# antduino.net
KiCad netlist of a schematic drawn in EAGLE
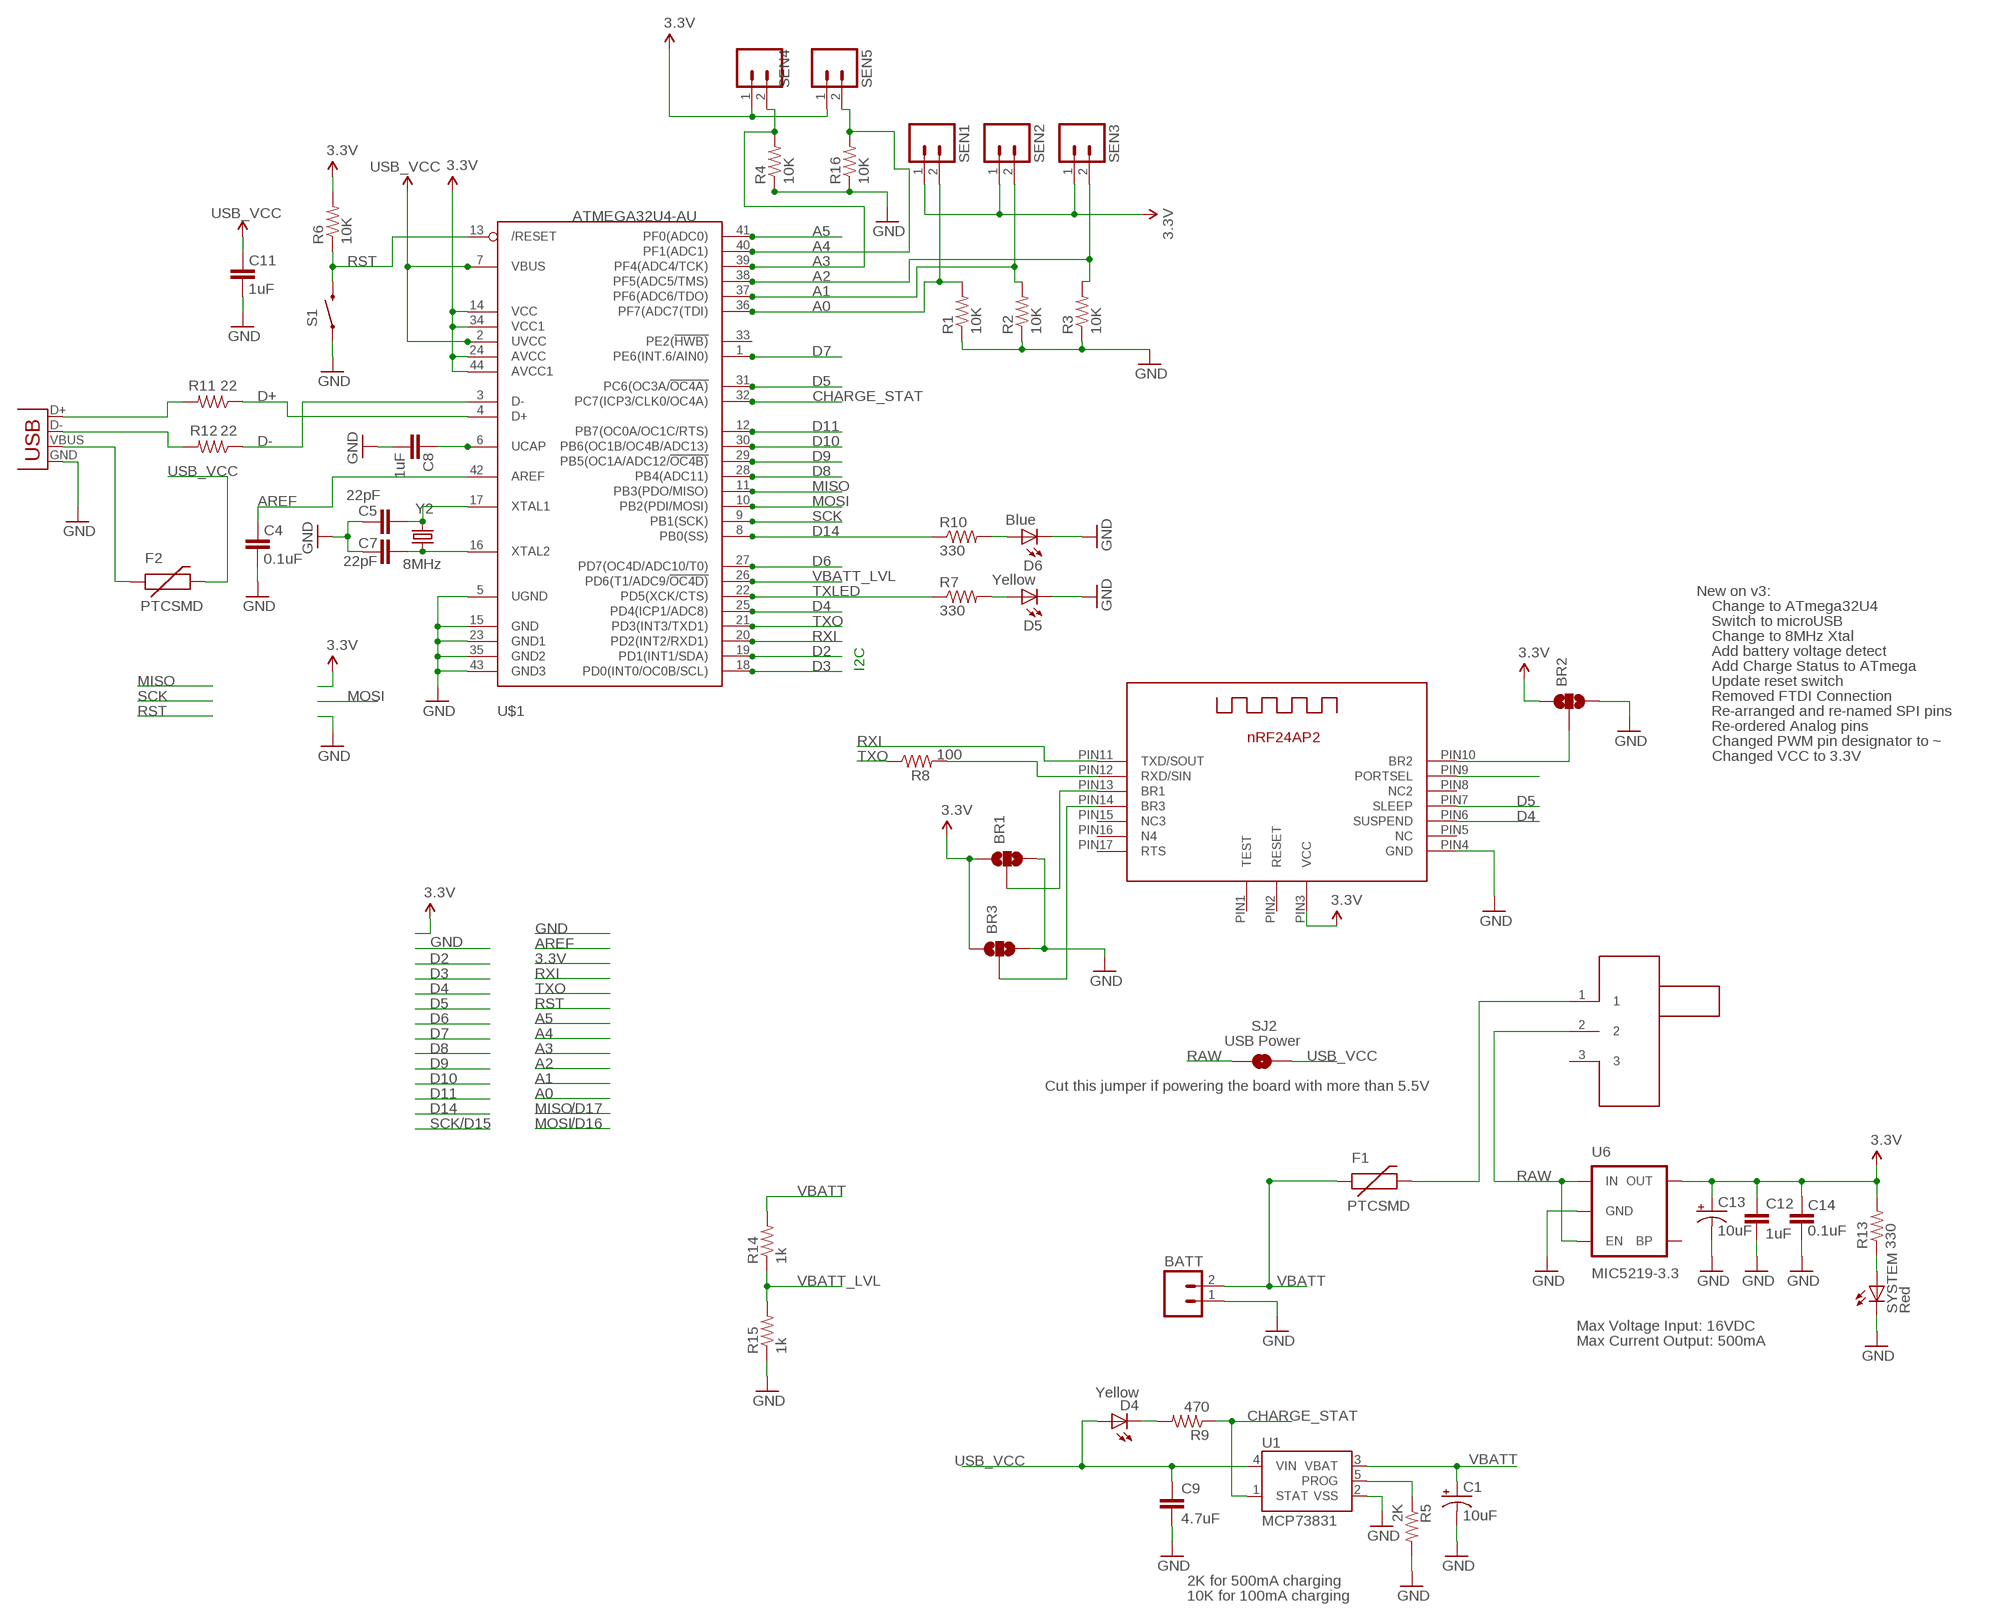
[diagram p0: schematic, sheet 1]

(export (version "E")
  (design (tool "Eeschema 10.0.6"))
  (components
    (comp (ref "BATT")
      (value "M02PTH")
      (footprint "eagle-import:1X02")
      (libsource (lib "eagle-import") (part "M02PTH"))
    )
    (comp (ref "BR1")
      (value "SOLDERJUMPER_2WAY-OLDS")
      (footprint "eagle-import:SJ_3")
      (libsource (lib "eagle-import") (part "SOLDERJUMPER_2WAY-OLDS"))
    )
    (comp (ref "BR2")
      (value "SOLDERJUMPER_2WAY-OLDS")
      (footprint "eagle-import:SJ_3")
      (libsource (lib "eagle-import") (part "SOLDERJUMPER_2WAY-OLDS"))
    )
    (comp (ref "BR3")
      (value "SOLDERJUMPER_2WAY-OLDS")
      (footprint "eagle-import:SJ_3")
      (libsource (lib "eagle-import") (part "SOLDERJUMPER_2WAY-OLDS"))
    )
    (comp (ref "C1")
      (value "10uF")
      (footprint "eagle-import:EIA3216")
      (libsource (lib "eagle-import") (part "CAP_POL1206"))
    )
    (comp (ref "C4")
      (value "0.1uF")
      (footprint "eagle-import:0402-CAP")
      (libsource (lib "eagle-import") (part "CAP0402-CAP"))
    )
    (comp (ref "C5")
      (value "22pF")
      (footprint "eagle-import:0402-CAP")
      (libsource (lib "eagle-import") (part "CAP0402-CAP"))
    )
    (comp (ref "C7")
      (value "22pF")
      (footprint "eagle-import:0402-CAP")
      (libsource (lib "eagle-import") (part "CAP0402-CAP"))
    )
    (comp (ref "C8")
      (value "1uF")
      (footprint "eagle-import:0402-CAP")
      (libsource (lib "eagle-import") (part "CAP0402-CAP"))
    )
    (comp (ref "C9")
      (value "4.7uF")
      (footprint "eagle-import:0402-CAP")
      (libsource (lib "eagle-import") (part "CAP0402-CAP"))
    )
    (comp (ref "C11")
      (value "1uF")
      (footprint "eagle-import:0402-CAP")
      (libsource (lib "eagle-import") (part "CAP0402-CAP"))
    )
    (comp (ref "C12")
      (value "1uF")
      (footprint "eagle-import:0402-CAP")
      (libsource (lib "eagle-import") (part "CAP0402-CAP"))
    )
    (comp (ref "C13")
      (value "10uF")
      (footprint "eagle-import:EIA3216")
      (libsource (lib "eagle-import") (part "CAP_POL1206"))
    )
    (comp (ref "C14")
      (value "0.1uF")
      (footprint "eagle-import:0402-CAP")
      (libsource (lib "eagle-import") (part "CAP0402-CAP"))
    )
    (comp (ref "D4")
      (value "Yellow")
      (footprint "eagle-import:LED-0603")
      (libsource (lib "eagle-import") (part "LED0603"))
    )
    (comp (ref "D5")
      (value "Yellow")
      (footprint "eagle-import:LED-0603")
      (libsource (lib "eagle-import") (part "LED0603"))
    )
    (comp (ref "D6")
      (value "Blue")
      (footprint "eagle-import:LED-0603")
      (libsource (lib "eagle-import") (part "LED0603"))
    )
    (comp (ref "F1")
      (value "PTCSMD")
      (footprint "eagle-import:PTC-1206")
      (libsource (lib "eagle-import") (part "PTCSMD"))
    )
    (comp (ref "F2")
      (value "PTCSMD")
      (footprint "eagle-import:PTC-1206")
      (libsource (lib "eagle-import") (part "PTCSMD"))
    )
    (comp (ref "R1")
      (value "10K")
      (footprint "eagle-import:0402-RES")
      (libsource (lib "eagle-import") (part "RESISTOR0402-RES"))
    )
    (comp (ref "R2")
      (value "10K")
      (footprint "eagle-import:0402-RES")
      (libsource (lib "eagle-import") (part "RESISTOR0402-RES"))
    )
    (comp (ref "R3")
      (value "10K")
      (footprint "eagle-import:0402-RES")
      (libsource (lib "eagle-import") (part "RESISTOR0402-RES"))
    )
    (comp (ref "R4")
      (value "10K")
      (footprint "eagle-import:0402-RES")
      (libsource (lib "eagle-import") (part "RESISTOR0402-RES"))
    )
    (comp (ref "R5")
      (value "2K")
      (footprint "eagle-import:0402-RES")
      (libsource (lib "eagle-import") (part "RESISTOR0402-RES"))
    )
    (comp (ref "R6")
      (value "10K")
      (footprint "eagle-import:0402-RES")
      (libsource (lib "eagle-import") (part "RESISTOR0402-RES"))
    )
    (comp (ref "R7")
      (value "330")
      (footprint "eagle-import:0402-RES")
      (libsource (lib "eagle-import") (part "RESISTOR0402-RES"))
    )
    (comp (ref "R8")
      (value "100")
      (footprint "eagle-import:0402-RES")
      (libsource (lib "eagle-import") (part "RESISTOR0402-RES"))
    )
    (comp (ref "R9")
      (value "470")
      (footprint "eagle-import:0402-RES")
      (libsource (lib "eagle-import") (part "RESISTOR0402-RES"))
    )
    (comp (ref "R10")
      (value "330")
      (footprint "eagle-import:0402-RES")
      (libsource (lib "eagle-import") (part "RESISTOR0402-RES"))
    )
    (comp (ref "R11")
      (value "22")
      (footprint "eagle-import:0402-RES")
      (libsource (lib "eagle-import") (part "RESISTOR0402-RES"))
    )
    (comp (ref "R12")
      (value "22")
      (footprint "eagle-import:0402-RES")
      (libsource (lib "eagle-import") (part "RESISTOR0402-RES"))
    )
    (comp (ref "R13")
      (value "330")
      (footprint "eagle-import:0402-RES")
      (libsource (lib "eagle-import") (part "RESISTOR0402-RES"))
    )
    (comp (ref "R14")
      (value "1k")
      (footprint "eagle-import:0402-RES")
      (libsource (lib "eagle-import") (part "RESISTOR0402-RES"))
    )
    (comp (ref "R15")
      (value "1k")
      (footprint "eagle-import:0402-RES")
      (libsource (lib "eagle-import") (part "RESISTOR0402-RES"))
    )
    (comp (ref "R16")
      (value "10K")
      (footprint "eagle-import:0402-RES")
      (libsource (lib "eagle-import") (part "RESISTOR0402-RES"))
    )
    (comp (ref "S1")
      (value "SWITCH-MOMENTARY-2-SMD-1101NE")
      (footprint "eagle-import:TACTILE-SWITCH-1101NE")
      (libsource (lib "eagle-import") (part "SWITCH-MOMENTARY-2-SMD-1101NE"))
    )
    (comp (ref "SEN1")
      (value "M02-JST-2MM-SMT")
      (footprint "eagle-import:JST-2-SMD")
      (libsource (lib "eagle-import") (part "M02-JST-2MM-SMT"))
    )
    (comp (ref "SEN2")
      (value "M02-JST-2MM-SMT")
      (footprint "eagle-import:JST-2-SMD")
      (libsource (lib "eagle-import") (part "M02-JST-2MM-SMT"))
    )
    (comp (ref "SEN3")
      (value "M02-JST-2MM-SMT")
      (footprint "eagle-import:JST-2-SMD")
      (libsource (lib "eagle-import") (part "M02-JST-2MM-SMT"))
    )
    (comp (ref "SEN4")
      (value "M02PTH")
      (footprint "eagle-import:1X02")
      (libsource (lib "eagle-import") (part "M02PTH"))
    )
    (comp (ref "SEN5")
      (value "M02PTH")
      (footprint "eagle-import:1X02")
      (libsource (lib "eagle-import") (part "M02PTH"))
    )
    (comp (ref "SJ2")
      (value "USB Power")
      (footprint "eagle-import:SJ_2S-TRACE")
      (libsource (lib "eagle-import") (part "SOLDERJUMPERTRACE"))
    )
    (comp (ref "SYSTEM")
      (value "Red")
      (footprint "eagle-import:LED-0603")
      (libsource (lib "eagle-import") (part "LED0603"))
    )
    (comp (ref "U$1")
      (value "ATMEGA32U4-AU")
      (footprint "eagle-import:TQFP44")
      (libsource (lib "eagle-import") (part "ATMEGA32U4-AU"))
    )
    (comp (ref "U$2")
      (value "DECADE-NRF24AP2-PCB-ANT")
      (footprint "eagle-import:DECADE-NRF24AP2-PCB")
      (libsource (lib "eagle-import") (part "DECADE-NRF24AP2-PCB-ANT"))
    )
    (comp (ref "U$4")
      (value "DECADE-SW-SMALL")
      (footprint "eagle-import:DECADE-SW-SM")
      (libsource (lib "eagle-import") (part "DECADE-SW-SMALL"))
    )
    (comp (ref "U1")
      (value "MCP73831")
      (footprint "eagle-import:SOT23-5")
      (libsource (lib "eagle-import") (part "MCP73831"))
    )
    (comp (ref "U6")
      (value "MIC5219-3.3")
      (footprint "eagle-import:SOT23-5")
      (libsource (lib "eagle-import") (part "V_REG_LDOSMD"))
    )
    (comp (ref "X2")
      (value "USB-MICROB")
      (footprint "eagle-import:USB-MICROB")
      (libsource (lib "eagle-import") (part "USB-MICROB"))
    )
    (comp (ref "Y2")
      (value "8MHz")
      (footprint "eagle-import:CRYSTAL-SMD-5X3")
      (libsource (lib "eagle-import") (part "CRYSTAL5X3"))
    )
  )
  (nets
    (net (code "1") (name "/A0") (class "Default")
      (node (ref "R1") (pin "2") (pinfunction "2_2") (pintype "passive"))
      (node (ref "SEN1") (pin "2") (pinfunction "2_2") (pintype "passive"))
      (node (ref "U$1") (pin "36") (pinfunction "PF7(ADC7(TDI)_36") (pintype "bidirectional"))
    )
    (net (code "2") (name "/A1") (class "Default")
      (node (ref "R2") (pin "2") (pinfunction "2_2") (pintype "passive"))
      (node (ref "SEN2") (pin "2") (pinfunction "2_2") (pintype "passive"))
      (node (ref "U$1") (pin "37") (pinfunction "PF6(ADC6/TDO)_37") (pintype "bidirectional"))
    )
    (net (code "3") (name "/A2") (class "Default")
      (node (ref "R3") (pin "2") (pinfunction "2_2") (pintype "passive"))
      (node (ref "SEN3") (pin "2") (pinfunction "2_2") (pintype "passive"))
      (node (ref "U$1") (pin "38") (pinfunction "PF5(ADC5/TMS)_38") (pintype "bidirectional"))
    )
    (net (code "4") (name "/A3") (class "Default")
      (node (ref "R4") (pin "2") (pinfunction "2_2") (pintype "passive"))
      (node (ref "SEN4") (pin "2") (pinfunction "2_2") (pintype "passive"))
      (node (ref "U$1") (pin "39") (pinfunction "PF4(ADC4/TCK)_39") (pintype "bidirectional"))
    )
    (net (code "5") (name "/A4") (class "Default")
      (node (ref "R16") (pin "2") (pinfunction "2_2") (pintype "passive"))
      (node (ref "SEN5") (pin "2") (pinfunction "2_2") (pintype "passive"))
      (node (ref "U$1") (pin "40") (pinfunction "PF1(ADC1)_40") (pintype "bidirectional"))
    )
    (net (code "6") (name "/A5") (class "Default")
      (node (ref "U$1") (pin "41") (pinfunction "PF0(ADC0)_41") (pintype "bidirectional"))
    )
    (net (code "7") (name "/AREF") (class "Default")
      (node (ref "C4") (pin "2") (pinfunction "2_2") (pintype "passive"))
      (node (ref "U$1") (pin "42") (pinfunction "AREF_42") (pintype "bidirectional"))
    )
    (net (code "8") (name "/CHARGE_STAT") (class "Default")
      (node (ref "R9") (pin "1") (pinfunction "1_1") (pintype "passive"))
      (node (ref "U$1") (pin "32") (pinfunction "PC7(ICP3/CLK0/OC4A)_32") (pintype "bidirectional"))
      (node (ref "U1") (pin "1") (pinfunction "STAT_1") (pintype "output"))
    )
    (net (code "9") (name "/D+") (class "Default")
      (node (ref "R11") (pin "1") (pinfunction "1_1") (pintype "passive"))
      (node (ref "U$1") (pin "4") (pinfunction "D+_4") (pintype "bidirectional"))
    )
    (net (code "10") (name "/D-") (class "Default")
      (node (ref "R12") (pin "1") (pinfunction "1_1") (pintype "passive"))
      (node (ref "U$1") (pin "3") (pinfunction "D-_3") (pintype "bidirectional"))
    )
    (net (code "11") (name "/D2") (class "Default")
      (node (ref "U$1") (pin "19") (pinfunction "PD1(INT1/SDA)_19") (pintype "bidirectional"))
    )
    (net (code "12") (name "/D3") (class "Default")
      (node (ref "U$1") (pin "18") (pinfunction "PD0(INT0/OC0B/SCL)_18") (pintype "bidirectional"))
    )
    (net (code "13") (name "/D4") (class "Default")
      (node (ref "U$1") (pin "25") (pinfunction "PD4(ICP1/ADC8)_25") (pintype "bidirectional"))
      (node (ref "U$2") (pin "PIN6") (pinfunction "SUSPEND_PIN6") (pintype "bidirectional"))
    )
    (net (code "14") (name "/D5") (class "Default")
      (node (ref "U$1") (pin "31") (pinfunction "PC6(OC3A/~{OC4A})_31") (pintype "bidirectional"))
      (node (ref "U$2") (pin "PIN7") (pinfunction "SLEEP_PIN7") (pintype "bidirectional"))
    )
    (net (code "15") (name "/D6") (class "Default")
      (node (ref "U$1") (pin "27") (pinfunction "PD7(OC4D/ADC10/T0)_27") (pintype "bidirectional"))
    )
    (net (code "16") (name "/D7") (class "Default")
      (node (ref "U$1") (pin "1") (pinfunction "PE6(INT.6/AIN0)_1") (pintype "bidirectional"))
    )
    (net (code "17") (name "/D8") (class "Default")
      (node (ref "U$1") (pin "28") (pinfunction "PB4(ADC11)_28") (pintype "bidirectional"))
    )
    (net (code "18") (name "/D9") (class "Default")
      (node (ref "U$1") (pin "29") (pinfunction "PB5(OC1A/ADC12/~{OC4B})_29") (pintype "bidirectional"))
    )
    (net (code "19") (name "/D10") (class "Default")
      (node (ref "U$1") (pin "30") (pinfunction "PB6(OC1B/OC4B/ADC13)_30") (pintype "bidirectional"))
    )
    (net (code "20") (name "/D11") (class "Default")
      (node (ref "U$1") (pin "12") (pinfunction "PB7(OC0A/OC1C/RTS)_12") (pintype "bidirectional"))
    )
    (net (code "21") (name "/D14") (class "Default")
      (node (ref "R10") (pin "1") (pinfunction "1_1") (pintype "passive"))
      (node (ref "U$1") (pin "8") (pinfunction "PB0(SS)_8") (pintype "bidirectional"))
    )
    (net (code "22") (name "/MISO") (class "Default")
      (node (ref "U$1") (pin "11") (pinfunction "PB3(PDO/MISO)_11") (pintype "bidirectional"))
    )
    (net (code "23") (name "/MOSI") (class "Default")
      (node (ref "U$1") (pin "10") (pinfunction "PB2(PDI/MOSI)_10") (pintype "bidirectional"))
    )
    (net (code "24") (name "/RAW") (class "Default")
      (node (ref "SJ2") (pin "1") (pinfunction "1_1") (pintype "passive"))
      (node (ref "U$4") (pin "2") (pinfunction "2_2") (pintype "bidirectional"))
      (node (ref "U6") (pin "1") (pinfunction "IN_1") (pintype "input"))
      (node (ref "U6") (pin "3") (pinfunction "EN_3") (pintype "input"))
    )
    (net (code "25") (name "/RST") (class "Default")
      (node (ref "R6") (pin "1") (pinfunction "1_1") (pintype "passive"))
      (node (ref "S1") (pin "P$2") (pinfunction "2_P$2") (pintype "passive"))
      (node (ref "U$1") (pin "13") (pinfunction "/RESET_13") (pintype "bidirectional"))
    )
    (net (code "26") (name "/RXI") (class "Default")
      (node (ref "U$1") (pin "20") (pinfunction "PD2(INT2/RXD1)_20") (pintype "bidirectional"))
      (node (ref "U$2") (pin "PIN11") (pinfunction "TXD/SOUT_PIN11") (pintype "bidirectional"))
    )
    (net (code "27") (name "/SCK") (class "Default")
      (node (ref "U$1") (pin "9") (pinfunction "PB1(SCK)_9") (pintype "bidirectional"))
    )
    (net (code "28") (name "/TXLED") (class "Default")
      (node (ref "R7") (pin "1") (pinfunction "1_1") (pintype "passive"))
      (node (ref "U$1") (pin "22") (pinfunction "PD5(XCK/CTS)_22") (pintype "bidirectional"))
    )
    (net (code "29") (name "/TXO") (class "Default")
      (node (ref "R8") (pin "1") (pinfunction "1_1") (pintype "passive"))
      (node (ref "U$1") (pin "21") (pinfunction "PD3(INT3/TXD1)_21") (pintype "bidirectional"))
    )
    (net (code "30") (name "/VBATT") (class "Default")
      (node (ref "BATT") (pin "2") (pinfunction "2_2") (pintype "passive"))
      (node (ref "C1") (pin "A") (pinfunction "+_A") (pintype "passive"))
      (node (ref "F1") (pin "1") (pinfunction "1_1") (pintype "bidirectional"))
      (node (ref "R14") (pin "2") (pinfunction "2_2") (pintype "passive"))
      (node (ref "U1") (pin "3") (pinfunction "VBAT_3") (pintype "power_in"))
    )
    (net (code "31") (name "/VBATT_LVL") (class "Default")
      (node (ref "R14") (pin "1") (pinfunction "1_1") (pintype "passive"))
      (node (ref "R15") (pin "2") (pinfunction "2_2") (pintype "passive"))
      (node (ref "U$1") (pin "26") (pinfunction "PD6(T1/ADC9/~{OC4D})_26") (pintype "bidirectional"))
    )
    (net (code "32") (name "3.3V") (class "Default")
      (node (ref "BR1") (pin "1") (pinfunction "1_1") (pintype "passive"))
      (node (ref "BR2") (pin "1") (pinfunction "1_1") (pintype "passive"))
      (node (ref "BR3") (pin "1") (pinfunction "1_1") (pintype "passive"))
      (node (ref "C12") (pin "1") (pinfunction "1_1") (pintype "passive"))
      (node (ref "C13") (pin "A") (pinfunction "+_A") (pintype "passive"))
      (node (ref "C14") (pin "2") (pinfunction "2_2") (pintype "passive"))
      (node (ref "R13") (pin "2") (pinfunction "2_2") (pintype "passive"))
      (node (ref "R6") (pin "2") (pinfunction "2_2") (pintype "passive"))
      (node (ref "SEN1") (pin "1") (pinfunction "1_1") (pintype "passive"))
      (node (ref "SEN2") (pin "1") (pinfunction "1_1") (pintype "passive"))
      (node (ref "SEN3") (pin "1") (pinfunction "1_1") (pintype "passive"))
      (node (ref "SEN4") (pin "1") (pinfunction "1_1") (pintype "passive"))
      (node (ref "SEN5") (pin "1") (pinfunction "1_1") (pintype "passive"))
      (node (ref "U$1") (pin "14") (pinfunction "VCC_14") (pintype "bidirectional"))
      (node (ref "U$1") (pin "24") (pinfunction "AVCC_24") (pintype "bidirectional"))
      (node (ref "U$1") (pin "34") (pinfunction "VCC1_34") (pintype "bidirectional"))
      (node (ref "U$1") (pin "44") (pinfunction "AVCC1_44") (pintype "bidirectional"))
      (node (ref "U$2") (pin "PIN3") (pinfunction "VCC_PIN3") (pintype "bidirectional"))
      (node (ref "U6") (pin "5") (pinfunction "OUT_5") (pintype "passive"))
    )
    (net (code "33") (name "GND") (class "Default")
      (node (ref "BATT") (pin "1") (pinfunction "1_1") (pintype "passive"))
      (node (ref "BR1") (pin "3") (pinfunction "3_3") (pintype "passive"))
      (node (ref "BR2") (pin "3") (pinfunction "3_3") (pintype "passive"))
      (node (ref "BR3") (pin "3") (pinfunction "3_3") (pintype "passive"))
      (node (ref "C1") (pin "C") (pinfunction "-_C") (pintype "passive"))
      (node (ref "C11") (pin "1") (pinfunction "1_1") (pintype "passive"))
      (node (ref "C12") (pin "2") (pinfunction "2_2") (pintype "passive"))
      (node (ref "C13") (pin "C") (pinfunction "-_C") (pintype "passive"))
      (node (ref "C14") (pin "1") (pinfunction "1_1") (pintype "passive"))
      (node (ref "C4") (pin "1") (pinfunction "1_1") (pintype "passive"))
      (node (ref "C5") (pin "2") (pinfunction "2_2") (pintype "passive"))
      (node (ref "C7") (pin "2") (pinfunction "2_2") (pintype "passive"))
      (node (ref "C8") (pin "1") (pinfunction "1_1") (pintype "passive"))
      (node (ref "C9") (pin "2") (pinfunction "2_2") (pintype "passive"))
      (node (ref "D5") (pin "C") (pinfunction "C_C") (pintype "passive"))
      (node (ref "D6") (pin "C") (pinfunction "C_C") (pintype "passive"))
      (node (ref "R1") (pin "1") (pinfunction "1_1") (pintype "passive"))
      (node (ref "R15") (pin "1") (pinfunction "1_1") (pintype "passive"))
      (node (ref "R16") (pin "1") (pinfunction "1_1") (pintype "passive"))
      (node (ref "R2") (pin "1") (pinfunction "1_1") (pintype "passive"))
      (node (ref "R3") (pin "1") (pinfunction "1_1") (pintype "passive"))
      (node (ref "R4") (pin "1") (pinfunction "1_1") (pintype "passive"))
      (node (ref "R5") (pin "2") (pinfunction "2_2") (pintype "passive"))
      (node (ref "S1") (pin "P$1") (pinfunction "1_P$1") (pintype "passive"))
      (node (ref "SYSTEM") (pin "C") (pinfunction "C_C") (pintype "passive"))
      (node (ref "U$1") (pin "15") (pinfunction "GND_15") (pintype "bidirectional"))
      (node (ref "U$1") (pin "23") (pinfunction "GND1_23") (pintype "bidirectional"))
      (node (ref "U$1") (pin "35") (pinfunction "GND2_35") (pintype "bidirectional"))
      (node (ref "U$1") (pin "43") (pinfunction "GND3_43") (pintype "bidirectional"))
      (node (ref "U$1") (pin "5") (pinfunction "UGND_5") (pintype "bidirectional"))
      (node (ref "U$2") (pin "PIN4") (pinfunction "GND_PIN4") (pintype "bidirectional"))
      (node (ref "U1") (pin "2") (pinfunction "VSS_2") (pintype "power_in"))
      (node (ref "U6") (pin "2") (pinfunction "GND_2") (pintype "input"))
      (node (ref "X2") (pin "GND") (pinfunction "GND_GND") (pintype "bidirectional"))
    )
    (net (code "34") (name "Net-(D4-PadC)") (class "Default")
      (node (ref "D4") (pin "C") (pinfunction "C_C") (pintype "passive"))
      (node (ref "R9") (pin "2") (pinfunction "2_2") (pintype "passive"))
    )
    (net (code "35") (name "Net-(D5-PadA)") (class "Default")
      (node (ref "D5") (pin "A") (pinfunction "A_A") (pintype "passive"))
      (node (ref "R7") (pin "2") (pinfunction "2_2") (pintype "passive"))
    )
    (net (code "36") (name "Net-(D6-PadA)") (class "Default")
      (node (ref "D6") (pin "A") (pinfunction "A_A") (pintype "passive"))
      (node (ref "R10") (pin "2") (pinfunction "2_2") (pintype "passive"))
    )
    (net (code "37") (name "Net-(F1-Pad2)") (class "Default")
      (node (ref "F1") (pin "2") (pinfunction "2_2") (pintype "bidirectional"))
      (node (ref "U$4") (pin "1") (pinfunction "1_1") (pintype "bidirectional"))
    )
    (net (code "38") (name "Net-(F2-Pad1)") (class "Default")
      (node (ref "F2") (pin "1") (pinfunction "1_1") (pintype "bidirectional"))
      (node (ref "X2") (pin "VBUS") (pinfunction "VBUS_VBUS") (pintype "bidirectional"))
    )
    (net (code "39") (name "Net-(R11-Pad2)") (class "Default")
      (node (ref "R11") (pin "2") (pinfunction "2_2") (pintype "passive"))
      (node (ref "X2") (pin "D+") (pinfunction "D+_D+") (pintype "bidirectional"))
    )
    (net (code "40") (name "Net-(R12-Pad2)") (class "Default")
      (node (ref "R12") (pin "2") (pinfunction "2_2") (pintype "passive"))
      (node (ref "X2") (pin "D-") (pinfunction "D-_D-") (pintype "bidirectional"))
    )
    (net (code "41") (name "Net-(R13-Pad1)") (class "Default")
      (node (ref "R13") (pin "1") (pinfunction "1_1") (pintype "passive"))
      (node (ref "SYSTEM") (pin "A") (pinfunction "A_A") (pintype "passive"))
    )
    (net (code "42") (name "Net-(U$1-UCAP)") (class "Default")
      (node (ref "C8") (pin "2") (pinfunction "2_2") (pintype "passive"))
      (node (ref "U$1") (pin "6") (pinfunction "UCAP_6") (pintype "bidirectional"))
    )
    (net (code "43") (name "Net-(U$1-XTAL1)") (class "Default")
      (node (ref "C5") (pin "1") (pinfunction "1_1") (pintype "passive"))
      (node (ref "U$1") (pin "17") (pinfunction "XTAL1_17") (pintype "bidirectional"))
      (node (ref "Y2") (pin "3") (pinfunction "2_3") (pintype "passive"))
    )
    (net (code "44") (name "Net-(U$1-XTAL2)") (class "Default")
      (node (ref "C7") (pin "1") (pinfunction "1_1") (pintype "passive"))
      (node (ref "U$1") (pin "16") (pinfunction "XTAL2_16") (pintype "bidirectional"))
      (node (ref "Y2") (pin "1") (pinfunction "1_1") (pintype "passive"))
    )
    (net (code "45") (name "Net-(U$2-BR1)") (class "Default")
      (node (ref "BR1") (pin "2") (pinfunction "2_2") (pintype "passive"))
      (node (ref "U$2") (pin "PIN13") (pinfunction "BR1_PIN13") (pintype "bidirectional"))
    )
    (net (code "46") (name "Net-(U$2-BR2)") (class "Default")
      (node (ref "BR2") (pin "2") (pinfunction "2_2") (pintype "passive"))
      (node (ref "U$2") (pin "PIN10") (pinfunction "BR2_PIN10") (pintype "bidirectional"))
    )
    (net (code "47") (name "Net-(U$2-BR3)") (class "Default")
      (node (ref "BR3") (pin "2") (pinfunction "2_2") (pintype "passive"))
      (node (ref "U$2") (pin "PIN14") (pinfunction "BR3_PIN14") (pintype "bidirectional"))
    )
    (net (code "48") (name "Net-(U$2-RXD{slash}SIN)") (class "Default")
      (node (ref "R8") (pin "2") (pinfunction "2_2") (pintype "passive"))
      (node (ref "U$2") (pin "PIN12") (pinfunction "RXD/SIN_PIN12") (pintype "bidirectional"))
    )
    (net (code "49") (name "Net-(U1-PROG)") (class "Default")
      (node (ref "R5") (pin "1") (pinfunction "1_1") (pintype "passive"))
      (node (ref "U1") (pin "5") (pinfunction "PROG_5") (pintype "input"))
    )
    (net (code "50") (name "USB_VCC") (class "Default")
      (node (ref "C11") (pin "2") (pinfunction "2_2") (pintype "passive"))
      (node (ref "C9") (pin "1") (pinfunction "1_1") (pintype "passive"))
      (node (ref "D4") (pin "A") (pinfunction "A_A") (pintype "passive"))
      (node (ref "F2") (pin "2") (pinfunction "2_2") (pintype "bidirectional"))
      (node (ref "SJ2") (pin "2") (pinfunction "2_2") (pintype "passive"))
      (node (ref "U$1") (pin "2") (pinfunction "UVCC_2") (pintype "bidirectional"))
      (node (ref "U$1") (pin "7") (pinfunction "VBUS_7") (pintype "bidirectional"))
      (node (ref "U1") (pin "4") (pinfunction "VIN_4") (pintype "power_in"))
    )
    (net (code "51") (name "unconnected-(U$1-PE2(~{HWB})-Pad33)") (class "Default")
      (node (ref "U$1") (pin "33") (pinfunction "PE2(~{HWB})_33") (pintype "bidirectional"))
    )
    (net (code "52") (name "unconnected-(U$2-N4-PadPIN16)") (class "Default")
      (node (ref "U$2") (pin "PIN16") (pinfunction "N4_PIN16") (pintype "bidirectional"))
    )
    (net (code "53") (name "unconnected-(U$2-NC-PadPIN5)") (class "Default")
      (node (ref "U$2") (pin "PIN5") (pinfunction "NC_PIN5") (pintype "bidirectional"))
    )
    (net (code "54") (name "unconnected-(U$2-NC2-PadPIN8)") (class "Default")
      (node (ref "U$2") (pin "PIN8") (pinfunction "NC2_PIN8") (pintype "bidirectional"))
    )
    (net (code "55") (name "unconnected-(U$2-NC3-PadPIN15)") (class "Default")
      (node (ref "U$2") (pin "PIN15") (pinfunction "NC3_PIN15") (pintype "bidirectional"))
    )
    (net (code "56") (name "unconnected-(U$2-PORTSEL-PadPIN9)") (class "Default")
      (node (ref "U$2") (pin "PIN9") (pinfunction "PORTSEL_PIN9") (pintype "bidirectional"))
    )
    (net (code "57") (name "unconnected-(U$2-RESET-PadPIN2)") (class "Default")
      (node (ref "U$2") (pin "PIN2") (pinfunction "RESET_PIN2") (pintype "bidirectional"))
    )
    (net (code "58") (name "unconnected-(U$2-RTS-PadPIN17)") (class "Default")
      (node (ref "U$2") (pin "PIN17") (pinfunction "RTS_PIN17") (pintype "bidirectional"))
    )
    (net (code "59") (name "unconnected-(U$2-TEST-PadPIN1)") (class "Default")
      (node (ref "U$2") (pin "PIN1") (pinfunction "TEST_PIN1") (pintype "bidirectional"))
    )
    (net (code "60") (name "unconnected-(U$4-Pad3)") (class "Default")
      (node (ref "U$4") (pin "3") (pinfunction "3_3") (pintype "bidirectional"))
    )
    (net (code "61") (name "unconnected-(U6-BP-Pad4)") (class "Default")
      (node (ref "U6") (pin "4") (pinfunction "BP_4") (pintype "input"))
    )
  )
)
